# MCU.net
KiCad netlist of a schematic drawn in Altium Designer
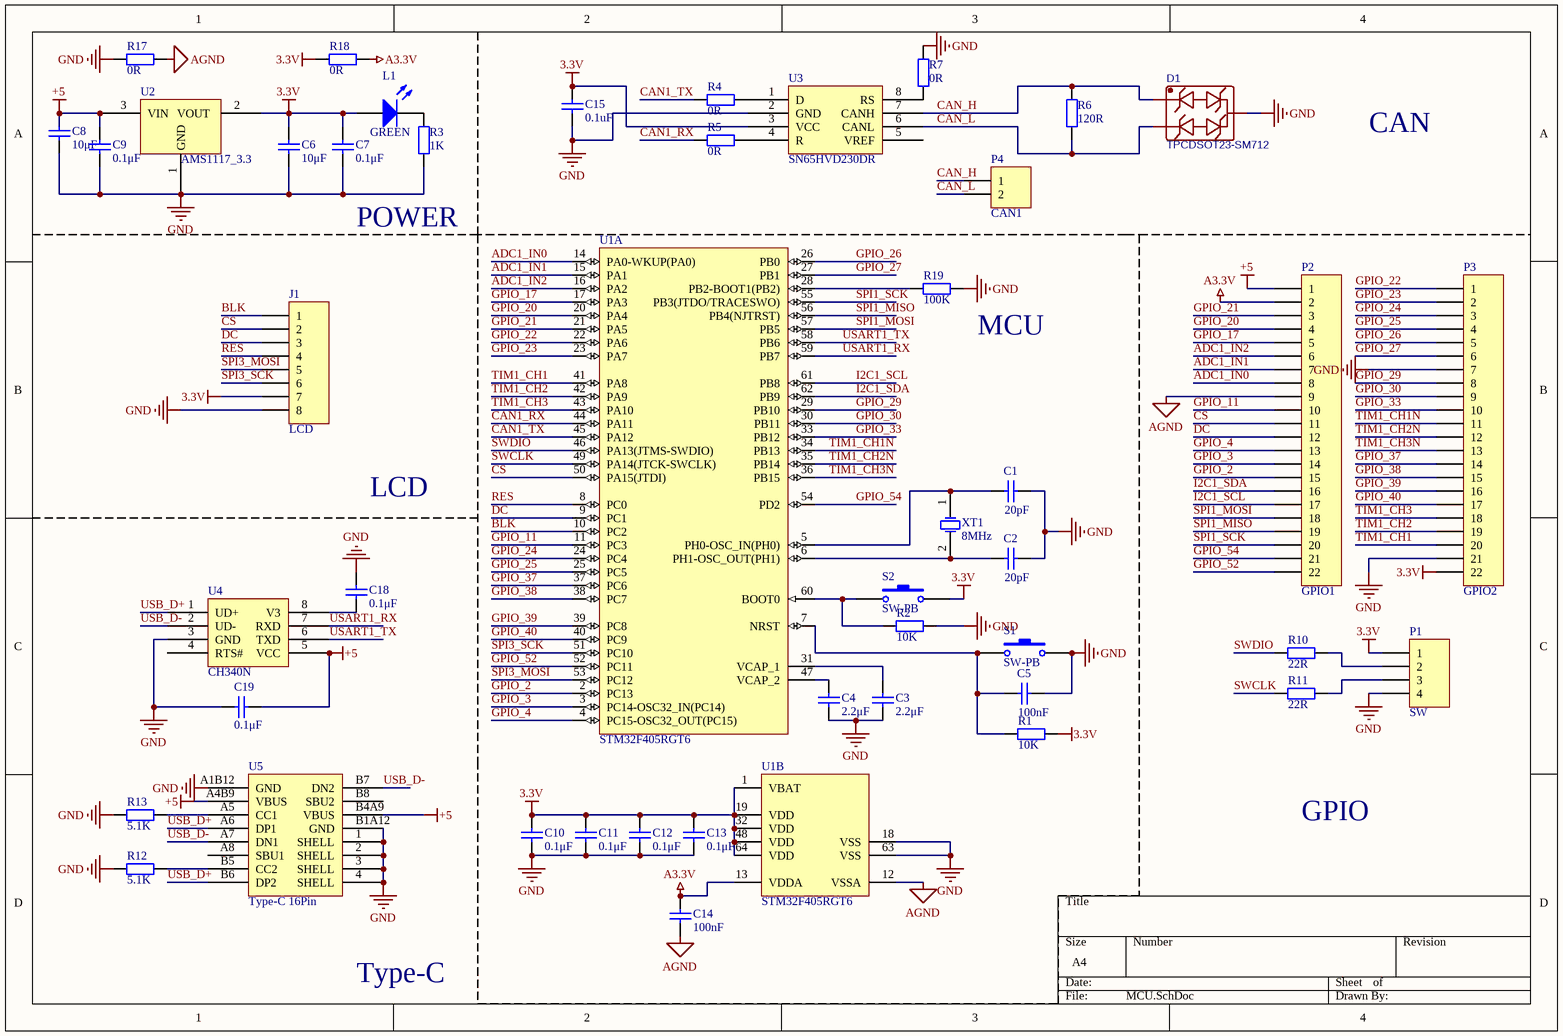
[diagram p0: MCU.SchDoc]

(export (version "E")
  (design (tool "Eeschema 10.0.6"))
  (components
    (comp (ref "C1")
      (value "20pF")
      (footprint "0402")
      (description "Capacitor (Semiconductor SIM Model)")
      (fields (field (name "PUBLISHER") "Altium Limited"))
      (libsource (lib "Miscellaneous Devices") (part "Cap Semi"))
    )
    (comp (ref "C2")
      (value "20pF")
      (footprint "0402")
      (description "Capacitor (Semiconductor SIM Model)")
      (fields (field (name "PUBLISHER") "Altium Limited"))
      (libsource (lib "Miscellaneous Devices") (part "Cap Semi"))
    )
    (comp (ref "C3")
      (value "2.2μF")
      (footprint "0402")
      (description "Capacitor (Semiconductor SIM Model)")
      (fields (field (name "PUBLISHER") "Altium Limited"))
      (libsource (lib "Miscellaneous Devices") (part "Cap Semi"))
    )
    (comp (ref "C4")
      (value "2.2μF")
      (footprint "0402")
      (description "Capacitor (Semiconductor SIM Model)")
      (fields (field (name "PUBLISHER") "Altium Limited"))
      (libsource (lib "Miscellaneous Devices") (part "Cap Semi"))
    )
    (comp (ref "C5")
      (value "100nF")
      (footprint "0402")
      (description "Capacitor (Semiconductor SIM Model)")
      (fields (field (name "PUBLISHER") "Altium Limited"))
      (libsource (lib "Miscellaneous Devices") (part "Cap Semi"))
    )
    (comp (ref "C6")
      (value "10μF")
      (footprint "0402")
      (description "Capacitor (Semiconductor SIM Model)")
      (fields (field (name "PUBLISHER") "Altium Limited"))
      (libsource (lib "Miscellaneous Devices") (part "Cap Semi"))
    )
    (comp (ref "C7")
      (value "0.1μF")
      (footprint "0402")
      (description "Capacitor (Semiconductor SIM Model)")
      (fields (field (name "PUBLISHER") "Altium Limited"))
      (libsource (lib "Miscellaneous Devices") (part "Cap Semi"))
    )
    (comp (ref "C8")
      (value "10μF")
      (footprint "0402")
      (description "Capacitor (Semiconductor SIM Model)")
      (fields (field (name "PUBLISHER") "Altium Limited"))
      (libsource (lib "Miscellaneous Devices") (part "Cap Semi"))
    )
    (comp (ref "C9")
      (value "0.1μF")
      (footprint "0402")
      (description "Capacitor (Semiconductor SIM Model)")
      (fields (field (name "PUBLISHER") "Altium Limited"))
      (libsource (lib "Miscellaneous Devices") (part "Cap Semi"))
    )
    (comp (ref "C10")
      (value "0.1μF")
      (footprint "0402")
      (description "Capacitor (Semiconductor SIM Model)")
      (fields (field (name "PUBLISHER") "Altium Limited"))
      (libsource (lib "Miscellaneous Devices") (part "Cap Semi"))
    )
    (comp (ref "C11")
      (value "0.1μF")
      (footprint "0402")
      (description "Capacitor (Semiconductor SIM Model)")
      (fields (field (name "PUBLISHER") "Altium Limited"))
      (libsource (lib "Miscellaneous Devices") (part "Cap Semi"))
    )
    (comp (ref "C12")
      (value "0.1μF")
      (footprint "0402")
      (description "Capacitor (Semiconductor SIM Model)")
      (fields (field (name "PUBLISHER") "Altium Limited"))
      (libsource (lib "Miscellaneous Devices") (part "Cap Semi"))
    )
    (comp (ref "C13")
      (value "0.1μF")
      (footprint "0402")
      (description "Capacitor (Semiconductor SIM Model)")
      (fields (field (name "PUBLISHER") "Altium Limited"))
      (libsource (lib "Miscellaneous Devices") (part "Cap Semi"))
    )
    (comp (ref "C14")
      (value "100nF")
      (footprint "0402")
      (description "Capacitor (Semiconductor SIM Model)")
      (fields (field (name "PUBLISHER") "Altium Limited"))
      (libsource (lib "Miscellaneous Devices") (part "Cap Semi"))
    )
    (comp (ref "C15")
      (value "0.1uF")
      (footprint "0402")
      (description "Capacitor (Semiconductor SIM Model)")
      (fields (field (name "PUBLISHER") "Altium Limited"))
      (libsource (lib "Miscellaneous Devices") (part "Cap Semi"))
    )
    (comp (ref "C18")
      (value "0.1μF")
      (footprint "0402")
      (description "Capacitor (Semiconductor SIM Model)")
      (fields (field (name "PUBLISHER") "Altium Limited"))
      (libsource (lib "Miscellaneous Devices") (part "Cap Semi"))
    )
    (comp (ref "C19")
      (value "0.1μF")
      (footprint "0402")
      (description "Capacitor (Semiconductor SIM Model)")
      (fields (field (name "PUBLISHER") "Altium Limited"))
      (libsource (lib "Miscellaneous Devices") (part "Cap Semi"))
    )
    (comp (ref "D1")
      (value "TPCDSOT23-SM712")
      (footprint "SOT23-3_L2.9-W1.6-P1.90-LS2.8-BR")
      (fields (field (name "BOM_SUPPLIER PART") "C558433") (field (name "CONTRIBUTOR") "LCSC"))
      (libsource (lib "Schlib1") (part "TPCDSOT23-SM712"))
    )
    (comp (ref "J1")
      (value "LCD")
      (footprint "HDR1X8")
      (description "Header, 8-Pin")
      (fields (field (name "PUBLISHER") "Altium Limited"))
      (libsource (lib "Miscellaneous Connectors") (part "Header 8"))
    )
    (comp (ref "L1")
      (value "GREEN")
      (footprint "0402-A")
      (description "Typical RED, GREEN, YELLOW, AMBER GaAs LED")
      (fields (field (name "PUBLISHER") "Altium Limited"))
      (libsource (lib "Miscellaneous Devices") (part "LED2"))
    )
    (comp (ref "P1")
      (value "SW")
      (footprint "HDR1X4")
      (description "Header, 4-Pin")
      (fields (field (name "PUBLISHER") "Altium Limited"))
      (libsource (lib "Miscellaneous Connectors") (part "Header 4"))
    )
    (comp (ref "P2")
      (value "GPIO1")
      (footprint "HDR1X22")
      (description "Header, 22-Pin")
      (fields (field (name "PUBLISHER") "Altium Limited"))
      (libsource (lib "Miscellaneous Connectors") (part "Header 22"))
    )
    (comp (ref "P3")
      (value "GPIO2")
      (footprint "HDR1X22")
      (description "Header, 22-Pin")
      (fields (field (name "PUBLISHER") "Altium Limited"))
      (libsource (lib "Miscellaneous Connectors") (part "Header 22"))
    )
    (comp (ref "P4")
      (value "CAN1")
      (footprint "FPC-SMD_2P-P2.00_DEALON_PH-2PWB")
      (description "Header, 2-Pin")
      (fields (field (name "PUBLISHER") "Altium Limited"))
      (libsource (lib "Miscellaneous Connectors") (part "Header 2"))
    )
    (comp (ref "R1")
      (value "10K")
      (footprint "0402")
      (description "Resistor")
      (fields (field (name "PUBLISHER") "Altium Limited"))
      (libsource (lib "") (part "Res2_1"))
    )
    (comp (ref "R2")
      (value "10K")
      (footprint "0402")
      (description "Resistor")
      (fields (field (name "PUBLISHER") "Altium Limited"))
      (libsource (lib "") (part "Res2_1"))
    )
    (comp (ref "R3")
      (value "1K")
      (footprint "0402")
      (description "Resistor")
      (fields (field (name "PUBLISHER") "Altium Limited"))
      (libsource (lib "Miscellaneous Devices") (part "Res2"))
    )
    (comp (ref "R4")
      (value "0R")
      (footprint "0402")
      (description "Resistor")
      (fields (field (name "PUBLISHER") "Altium Limited"))
      (libsource (lib "") (part "Res2_1"))
    )
    (comp (ref "R5")
      (value "0R")
      (footprint "0402")
      (description "Resistor")
      (fields (field (name "PUBLISHER") "Altium Limited"))
      (libsource (lib "") (part "Res2_1"))
    )
    (comp (ref "R6")
      (value "120R")
      (footprint "0402")
      (description "Resistor")
      (fields (field (name "PUBLISHER") "Altium Limited"))
      (libsource (lib "Miscellaneous Devices") (part "Res2"))
    )
    (comp (ref "R7")
      (value "0R")
      (footprint "0402")
      (description "Resistor")
      (fields (field (name "PUBLISHER") "Altium Limited"))
      (libsource (lib "Miscellaneous Devices") (part "Res2"))
    )
    (comp (ref "R10")
      (value "22R")
      (footprint "0402")
      (description "Resistor")
      (fields (field (name "PUBLISHER") "Altium Limited"))
      (libsource (lib "") (part "Res2_1"))
    )
    (comp (ref "R11")
      (value "22R")
      (footprint "0402")
      (description "Resistor")
      (fields (field (name "PUBLISHER") "Altium Limited"))
      (libsource (lib "") (part "Res2_1"))
    )
    (comp (ref "R12")
      (value "5.1K")
      (footprint "0402")
      (description "Resistor")
      (fields (field (name "PUBLISHER") "Altium Limited"))
      (libsource (lib "") (part "Res2_1"))
    )
    (comp (ref "R13")
      (value "5.1K")
      (footprint "0402")
      (description "Resistor")
      (fields (field (name "PUBLISHER") "Altium Limited"))
      (libsource (lib "") (part "Res2_1"))
    )
    (comp (ref "R17")
      (value "0R")
      (footprint "0402")
      (description "Resistor")
      (fields (field (name "PUBLISHER") "Altium Limited"))
      (libsource (lib "") (part "Res2_1"))
    )
    (comp (ref "R18")
      (value "0R")
      (footprint "0402")
      (description "Resistor")
      (fields (field (name "PUBLISHER") "Altium Limited"))
      (libsource (lib "") (part "Res2_1"))
    )
    (comp (ref "R19")
      (value "100K")
      (footprint "0402")
      (description "Resistor")
      (fields (field (name "PUBLISHER") "Altium Limited"))
      (libsource (lib "") (part "Res2_1"))
    )
    (comp (ref "S1")
      (value "SW-PB")
      (footprint "KEY-SMD_4P-L4.2-W3.2-P2.20-LS5.1-TL")
      (description "Switch")
      (fields (field (name "PUBLISHER") "Altium Limited"))
      (libsource (lib "Miscellaneous Devices") (part "SW-PB"))
    )
    (comp (ref "S2")
      (value "SW-PB")
      (footprint "KEY-SMD_4P-L4.2-W3.2-P2.20-LS5.1-TL")
      (description "Switch")
      (fields (field (name "PUBLISHER") "Altium Limited"))
      (libsource (lib "Miscellaneous Devices") (part "SW-PB"))
    )
    (comp (ref "U1")
      (value "STM32F405RGT6")
      (footprint "STM-LQFP64_N")
      (fields (field (name "MANUFACTURER") "STMicroelectronics"))
      (libsource (lib "STMicroelectronics STM32 F4") (part "STM32F405RGT6"))
    )
    (comp (ref "U2")
      (value "AMS1117_3.3")
      (footprint "SOT-89-3_L4.5-W2.5-P1.50-LS4.1-BL")
      (libsource (lib "Schlib1") (part "AMS1117_3.3 SOT-89"))
    )
    (comp (ref "U3")
      (value "SN65HVD230DR")
      (footprint "SN65HVD230DR-SOIC-8_L4.9-W3.9-P1.27-LS6.0-BL")
      (libsource (lib "Schlib1") (part "SN65HVD230DR"))
    )
    (comp (ref "U4")
      (value "CH340N")
      (footprint "CH340N-SOP-8_L4.9-W3.9-P1.27-LS6.0-BL")
      (libsource (lib "Schlib1") (part "CH340N"))
    )
    (comp (ref "U5")
      (value "Type-C 16Pin")
      (footprint "USB-C-SMD_TYPE-C16PIN")
      (libsource (lib "Schlib1") (part "Type-C 16Pin"))
    )
    (comp (ref "XT1")
      (value "8MHz")
      (footprint "OSC-SMD_L5.0-W3.2")
      (description "Crystal Oscillator")
      (fields (field (name "PUBLISHER") "Altium Limited"))
      (libsource (lib "Miscellaneous Devices") (part "XTAL"))
    )
  )
  (nets
    (net (code "1") (name "+5") (class "Default")
      (node (ref "C19") (pin "1") (pinfunction "1_1") (pintype "passive"))
      (node (ref "C8") (pin "2") (pinfunction "2_2") (pintype "passive"))
      (node (ref "C9") (pin "2") (pinfunction "2_2") (pintype "passive"))
      (node (ref "P2") (pin "1") (pinfunction "1_1") (pintype "passive"))
      (node (ref "U2") (pin "3") (pinfunction "VIN_3") (pintype "passive"))
      (node (ref "U4") (pin "5") (pinfunction "VCC_5") (pintype "passive"))
      (node (ref "U5") (pin "A4B9") (pinfunction "VBUS_A4B9") (pintype "passive"))
      (node (ref "U5") (pin "B4A9") (pinfunction "VBUS_B4A9") (pintype "passive"))
    )
    (net (code "2") (name "/ADC1_IN0") (class "Default")
      (node (ref "P2") (pin "8") (pinfunction "8_8") (pintype "passive"))
      (node (ref "U1") (pin "14") (pinfunction "PA0-WKUP(PA0)_14") (pintype "bidirectional"))
    )
    (net (code "3") (name "/ADC1_IN1") (class "Default")
      (node (ref "P2") (pin "7") (pinfunction "7_7") (pintype "passive"))
      (node (ref "U1") (pin "15") (pinfunction "PA1_15") (pintype "bidirectional"))
    )
    (net (code "4") (name "/ADC1_IN2") (class "Default")
      (node (ref "P2") (pin "6") (pinfunction "6_6") (pintype "passive"))
      (node (ref "U1") (pin "16") (pinfunction "PA2_16") (pintype "bidirectional"))
    )
    (net (code "5") (name "/BLK") (class "Default")
      (node (ref "J1") (pin "1") (pinfunction "1_1") (pintype "passive"))
      (node (ref "U1") (pin "10") (pinfunction "PC2_10") (pintype "bidirectional"))
    )
    (net (code "6") (name "/CAN1_RX") (class "Default")
      (node (ref "R5") (pin "1") (pinfunction "1_1") (pintype "passive"))
      (node (ref "U1") (pin "44") (pinfunction "PA11_44") (pintype "bidirectional"))
    )
    (net (code "7") (name "/CAN1_TX") (class "Default")
      (node (ref "R4") (pin "1") (pinfunction "1_1") (pintype "passive"))
      (node (ref "U1") (pin "45") (pinfunction "PA12_45") (pintype "bidirectional"))
    )
    (net (code "8") (name "/CAN_H") (class "Default")
      (node (ref "D1") (pin "1") (pinfunction "1_1") (pintype "passive"))
      (node (ref "P4") (pin "1") (pinfunction "1_1") (pintype "passive"))
      (node (ref "R6") (pin "2") (pinfunction "2_2") (pintype "passive"))
      (node (ref "U3") (pin "7") (pinfunction "CANH_7") (pintype "passive"))
    )
    (net (code "9") (name "/CAN_L") (class "Default")
      (node (ref "D1") (pin "2") (pinfunction "2_2") (pintype "passive"))
      (node (ref "P4") (pin "2") (pinfunction "2_2") (pintype "passive"))
      (node (ref "R6") (pin "1") (pinfunction "1_1") (pintype "passive"))
      (node (ref "U3") (pin "6") (pinfunction "CANL_6") (pintype "passive"))
    )
    (net (code "10") (name "/CS") (class "Default")
      (node (ref "J1") (pin "2") (pinfunction "2_2") (pintype "passive"))
      (node (ref "P2") (pin "11") (pinfunction "11_11") (pintype "passive"))
      (node (ref "U1") (pin "50") (pinfunction "PA15(JTDI)_50") (pintype "bidirectional"))
    )
    (net (code "11") (name "/DC") (class "Default")
      (node (ref "J1") (pin "3") (pinfunction "3_3") (pintype "passive"))
      (node (ref "P2") (pin "12") (pinfunction "12_12") (pintype "passive"))
      (node (ref "U1") (pin "9") (pinfunction "PC1_9") (pintype "bidirectional"))
    )
    (net (code "12") (name "/GPIO_2") (class "Default")
      (node (ref "P2") (pin "15") (pinfunction "15_15") (pintype "passive"))
      (node (ref "U1") (pin "2") (pinfunction "PC13_2") (pintype "bidirectional"))
    )
    (net (code "13") (name "/GPIO_3") (class "Default")
      (node (ref "P2") (pin "14") (pinfunction "14_14") (pintype "passive"))
      (node (ref "U1") (pin "3") (pinfunction "PC14-OSC32_IN(PC14)_3") (pintype "bidirectional"))
    )
    (net (code "14") (name "/GPIO_4") (class "Default")
      (node (ref "P2") (pin "13") (pinfunction "13_13") (pintype "passive"))
      (node (ref "U1") (pin "4") (pinfunction "PC15-OSC32_OUT(PC15)_4") (pintype "bidirectional"))
    )
    (net (code "15") (name "/GPIO_11") (class "Default")
      (node (ref "P2") (pin "10") (pinfunction "10_10") (pintype "passive"))
      (node (ref "U1") (pin "11") (pinfunction "PC3_11") (pintype "bidirectional"))
    )
    (net (code "16") (name "/GPIO_17") (class "Default")
      (node (ref "P2") (pin "5") (pinfunction "5_5") (pintype "passive"))
      (node (ref "U1") (pin "17") (pinfunction "PA3_17") (pintype "bidirectional"))
    )
    (net (code "17") (name "/GPIO_20") (class "Default")
      (node (ref "P2") (pin "4") (pinfunction "4_4") (pintype "passive"))
      (node (ref "U1") (pin "20") (pinfunction "PA4_20") (pintype "bidirectional"))
    )
    (net (code "18") (name "/GPIO_21") (class "Default")
      (node (ref "P2") (pin "3") (pinfunction "3_3") (pintype "passive"))
      (node (ref "U1") (pin "21") (pinfunction "PA5_21") (pintype "bidirectional"))
    )
    (net (code "19") (name "/GPIO_22") (class "Default")
      (node (ref "P3") (pin "1") (pinfunction "1_1") (pintype "passive"))
      (node (ref "U1") (pin "22") (pinfunction "PA6_22") (pintype "bidirectional"))
    )
    (net (code "20") (name "/GPIO_23") (class "Default")
      (node (ref "P3") (pin "2") (pinfunction "2_2") (pintype "passive"))
      (node (ref "U1") (pin "23") (pinfunction "PA7_23") (pintype "bidirectional"))
    )
    (net (code "21") (name "/GPIO_24") (class "Default")
      (node (ref "P3") (pin "3") (pinfunction "3_3") (pintype "passive"))
      (node (ref "U1") (pin "24") (pinfunction "PC4_24") (pintype "bidirectional"))
    )
    (net (code "22") (name "/GPIO_25") (class "Default")
      (node (ref "P3") (pin "4") (pinfunction "4_4") (pintype "passive"))
      (node (ref "U1") (pin "25") (pinfunction "PC5_25") (pintype "bidirectional"))
    )
    (net (code "23") (name "/GPIO_26") (class "Default")
      (node (ref "P3") (pin "5") (pinfunction "5_5") (pintype "passive"))
      (node (ref "U1") (pin "26") (pinfunction "PB0_26") (pintype "bidirectional"))
    )
    (net (code "24") (name "/GPIO_27") (class "Default")
      (node (ref "P3") (pin "6") (pinfunction "6_6") (pintype "passive"))
      (node (ref "U1") (pin "27") (pinfunction "PB1_27") (pintype "bidirectional"))
    )
    (net (code "25") (name "/GPIO_29") (class "Default")
      (node (ref "P3") (pin "8") (pinfunction "8_8") (pintype "passive"))
      (node (ref "U1") (pin "29") (pinfunction "PB10_29") (pintype "bidirectional"))
    )
    (net (code "26") (name "/GPIO_30") (class "Default")
      (node (ref "P3") (pin "9") (pinfunction "9_9") (pintype "passive"))
      (node (ref "U1") (pin "30") (pinfunction "PB11_30") (pintype "bidirectional"))
    )
    (net (code "27") (name "/GPIO_33") (class "Default")
      (node (ref "P3") (pin "10") (pinfunction "10_10") (pintype "passive"))
      (node (ref "U1") (pin "33") (pinfunction "PB12_33") (pintype "bidirectional"))
    )
    (net (code "28") (name "/GPIO_37") (class "Default")
      (node (ref "P3") (pin "14") (pinfunction "14_14") (pintype "passive"))
      (node (ref "U1") (pin "37") (pinfunction "PC6_37") (pintype "bidirectional"))
    )
    (net (code "29") (name "/GPIO_38") (class "Default")
      (node (ref "P3") (pin "15") (pinfunction "15_15") (pintype "passive"))
      (node (ref "U1") (pin "38") (pinfunction "PC7_38") (pintype "bidirectional"))
    )
    (net (code "30") (name "/GPIO_39") (class "Default")
      (node (ref "P3") (pin "16") (pinfunction "16_16") (pintype "passive"))
      (node (ref "U1") (pin "39") (pinfunction "PC8_39") (pintype "bidirectional"))
    )
    (net (code "31") (name "/GPIO_40") (class "Default")
      (node (ref "P3") (pin "17") (pinfunction "17_17") (pintype "passive"))
      (node (ref "U1") (pin "40") (pinfunction "PC9_40") (pintype "bidirectional"))
    )
    (net (code "32") (name "/GPIO_52") (class "Default")
      (node (ref "P2") (pin "22") (pinfunction "22_22") (pintype "passive"))
      (node (ref "U1") (pin "52") (pinfunction "PC11_52") (pintype "bidirectional"))
    )
    (net (code "33") (name "/GPIO_54") (class "Default")
      (node (ref "P2") (pin "21") (pinfunction "21_21") (pintype "passive"))
      (node (ref "U1") (pin "54") (pinfunction "PD2_54") (pintype "bidirectional"))
    )
    (net (code "34") (name "/I2C1_SCL") (class "Default")
      (node (ref "P2") (pin "17") (pinfunction "17_17") (pintype "passive"))
      (node (ref "U1") (pin "61") (pinfunction "PB8_61") (pintype "bidirectional"))
    )
    (net (code "35") (name "/I2C1_SDA") (class "Default")
      (node (ref "P2") (pin "16") (pinfunction "16_16") (pintype "passive"))
      (node (ref "U1") (pin "62") (pinfunction "PB9_62") (pintype "bidirectional"))
    )
    (net (code "36") (name "/RES") (class "Default")
      (node (ref "J1") (pin "4") (pinfunction "4_4") (pintype "passive"))
      (node (ref "U1") (pin "8") (pinfunction "PC0_8") (pintype "bidirectional"))
    )
    (net (code "37") (name "/SPI1_MISO") (class "Default")
      (node (ref "P2") (pin "19") (pinfunction "19_19") (pintype "passive"))
      (node (ref "U1") (pin "56") (pinfunction "PB4(NJTRST)_56") (pintype "bidirectional"))
    )
    (net (code "38") (name "/SPI1_MOSI") (class "Default")
      (node (ref "P2") (pin "18") (pinfunction "18_18") (pintype "passive"))
      (node (ref "U1") (pin "57") (pinfunction "PB5_57") (pintype "bidirectional"))
    )
    (net (code "39") (name "/SPI1_SCK") (class "Default")
      (node (ref "P2") (pin "20") (pinfunction "20_20") (pintype "passive"))
      (node (ref "U1") (pin "55") (pinfunction "PB3(JTDO/TRACESWO)_55") (pintype "bidirectional"))
    )
    (net (code "40") (name "/SPI3_MOSI") (class "Default")
      (node (ref "J1") (pin "5") (pinfunction "5_5") (pintype "passive"))
      (node (ref "U1") (pin "53") (pinfunction "PC12_53") (pintype "bidirectional"))
    )
    (net (code "41") (name "/SPI3_SCK") (class "Default")
      (node (ref "J1") (pin "6") (pinfunction "6_6") (pintype "passive"))
      (node (ref "U1") (pin "51") (pinfunction "PC10_51") (pintype "bidirectional"))
    )
    (net (code "42") (name "/SWCLK") (class "Default")
      (node (ref "R11") (pin "1") (pinfunction "1_1") (pintype "passive"))
      (node (ref "U1") (pin "49") (pinfunction "PA14(JTCK-SWCLK)_49") (pintype "bidirectional"))
    )
    (net (code "43") (name "/SWDIO") (class "Default")
      (node (ref "R10") (pin "1") (pinfunction "1_1") (pintype "passive"))
      (node (ref "U1") (pin "46") (pinfunction "PA13(JTMS-SWDIO)_46") (pintype "bidirectional"))
    )
    (net (code "44") (name "/TIM1_CH1") (class "Default")
      (node (ref "P3") (pin "20") (pinfunction "20_20") (pintype "passive"))
      (node (ref "U1") (pin "41") (pinfunction "PA8_41") (pintype "bidirectional"))
    )
    (net (code "45") (name "/TIM1_CH1N") (class "Default")
      (node (ref "P3") (pin "11") (pinfunction "11_11") (pintype "passive"))
      (node (ref "U1") (pin "34") (pinfunction "PB13_34") (pintype "bidirectional"))
    )
    (net (code "46") (name "/TIM1_CH2") (class "Default")
      (node (ref "P3") (pin "19") (pinfunction "19_19") (pintype "passive"))
      (node (ref "U1") (pin "42") (pinfunction "PA9_42") (pintype "bidirectional"))
    )
    (net (code "47") (name "/TIM1_CH2N") (class "Default")
      (node (ref "P3") (pin "12") (pinfunction "12_12") (pintype "passive"))
      (node (ref "U1") (pin "35") (pinfunction "PB14_35") (pintype "bidirectional"))
    )
    (net (code "48") (name "/TIM1_CH3") (class "Default")
      (node (ref "P3") (pin "18") (pinfunction "18_18") (pintype "passive"))
      (node (ref "U1") (pin "43") (pinfunction "PA10_43") (pintype "bidirectional"))
    )
    (net (code "49") (name "/TIM1_CH3N") (class "Default")
      (node (ref "P3") (pin "13") (pinfunction "13_13") (pintype "passive"))
      (node (ref "U1") (pin "36") (pinfunction "PB15_36") (pintype "bidirectional"))
    )
    (net (code "50") (name "/USART1_RX") (class "Default")
      (node (ref "U1") (pin "59") (pinfunction "PB7_59") (pintype "bidirectional"))
      (node (ref "U4") (pin "7") (pinfunction "RXD_7") (pintype "passive"))
    )
    (net (code "51") (name "/USART1_TX") (class "Default")
      (node (ref "U1") (pin "58") (pinfunction "PB6_58") (pintype "bidirectional"))
      (node (ref "U4") (pin "6") (pinfunction "TXD_6") (pintype "passive"))
    )
    (net (code "52") (name "/USB_D+") (class "Default")
      (node (ref "U4") (pin "1") (pinfunction "UD+_1") (pintype "passive"))
      (node (ref "U5") (pin "A6") (pinfunction "DP1_A6") (pintype "passive"))
      (node (ref "U5") (pin "B6") (pinfunction "DP2_B6") (pintype "passive"))
    )
    (net (code "53") (name "/USB_D-") (class "Default")
      (node (ref "U4") (pin "2") (pinfunction "UD-_2") (pintype "passive"))
      (node (ref "U5") (pin "A7") (pinfunction "DN1_A7") (pintype "passive"))
      (node (ref "U5") (pin "B7") (pinfunction "DN2_B7") (pintype "passive"))
    )
    (net (code "54") (name "3.3V") (class "Default")
      (node (ref "C10") (pin "2") (pinfunction "2_2") (pintype "passive"))
      (node (ref "C11") (pin "2") (pinfunction "2_2") (pintype "passive"))
      (node (ref "C12") (pin "2") (pinfunction "2_2") (pintype "passive"))
      (node (ref "C13") (pin "2") (pinfunction "2_2") (pintype "passive"))
      (node (ref "C15") (pin "2") (pinfunction "2_2") (pintype "passive"))
      (node (ref "C6") (pin "2") (pinfunction "2_2") (pintype "passive"))
      (node (ref "C7") (pin "2") (pinfunction "2_2") (pintype "passive"))
      (node (ref "J1") (pin "7") (pinfunction "7_7") (pintype "passive"))
      (node (ref "L1") (pin "1") (pinfunction "A_1") (pintype "passive"))
      (node (ref "P1") (pin "1") (pinfunction "1_1") (pintype "passive"))
      (node (ref "P3") (pin "22") (pinfunction "22_22") (pintype "passive"))
      (node (ref "R1") (pin "2") (pinfunction "2_2") (pintype "passive"))
      (node (ref "R18") (pin "1") (pinfunction "1_1") (pintype "passive"))
      (node (ref "S2") (pin "2") (pinfunction "2_2") (pintype "passive"))
      (node (ref "U1") (pin "1") (pinfunction "VBAT_1") (pintype "power_in"))
      (node (ref "U1") (pin "19") (pinfunction "VDD_19") (pintype "power_in"))
      (node (ref "U1") (pin "32") (pinfunction "VDD_32") (pintype "power_in"))
      (node (ref "U1") (pin "48") (pinfunction "VDD_48") (pintype "power_in"))
      (node (ref "U1") (pin "64") (pinfunction "VDD_64") (pintype "power_in"))
      (node (ref "U2") (pin "2") (pinfunction "VOUT_2") (pintype "passive"))
      (node (ref "U3") (pin "3") (pinfunction "VCC_3") (pintype "passive"))
    )
    (net (code "55") (name "A3.3V") (class "Default")
      (node (ref "C14") (pin "2") (pinfunction "2_2") (pintype "passive"))
      (node (ref "P2") (pin "2") (pinfunction "2_2") (pintype "passive"))
      (node (ref "R18") (pin "2") (pinfunction "2_2") (pintype "passive"))
      (node (ref "U1") (pin "13") (pinfunction "VDDA_13") (pintype "power_in"))
    )
    (net (code "56") (name "AGND") (class "Default")
      (node (ref "C14") (pin "1") (pinfunction "1_1") (pintype "passive"))
      (node (ref "P2") (pin "9") (pinfunction "9_9") (pintype "passive"))
      (node (ref "R17") (pin "2") (pinfunction "2_2") (pintype "passive"))
      (node (ref "U1") (pin "12") (pinfunction "VSSA_12") (pintype "power_in"))
    )
    (net (code "57") (name "GND") (class "Default")
      (node (ref "C1") (pin "2") (pinfunction "2_2") (pintype "passive"))
      (node (ref "C10") (pin "1") (pinfunction "1_1") (pintype "passive"))
      (node (ref "C11") (pin "1") (pinfunction "1_1") (pintype "passive"))
      (node (ref "C12") (pin "1") (pinfunction "1_1") (pintype "passive"))
      (node (ref "C13") (pin "1") (pinfunction "1_1") (pintype "passive"))
      (node (ref "C15") (pin "1") (pinfunction "1_1") (pintype "passive"))
      (node (ref "C18") (pin "2") (pinfunction "2_2") (pintype "passive"))
      (node (ref "C19") (pin "2") (pinfunction "2_2") (pintype "passive"))
      (node (ref "C2") (pin "2") (pinfunction "2_2") (pintype "passive"))
      (node (ref "C3") (pin "1") (pinfunction "1_1") (pintype "passive"))
      (node (ref "C4") (pin "1") (pinfunction "1_1") (pintype "passive"))
      (node (ref "C5") (pin "2") (pinfunction "2_2") (pintype "passive"))
      (node (ref "C6") (pin "1") (pinfunction "1_1") (pintype "passive"))
      (node (ref "C7") (pin "1") (pinfunction "1_1") (pintype "passive"))
      (node (ref "C8") (pin "1") (pinfunction "1_1") (pintype "passive"))
      (node (ref "C9") (pin "1") (pinfunction "1_1") (pintype "passive"))
      (node (ref "D1") (pin "3") (pinfunction "3_3") (pintype "passive"))
      (node (ref "J1") (pin "8") (pinfunction "8_8") (pintype "passive"))
      (node (ref "P1") (pin "4") (pinfunction "4_4") (pintype "passive"))
      (node (ref "P3") (pin "21") (pinfunction "21_21") (pintype "passive"))
      (node (ref "P3") (pin "7") (pinfunction "7_7") (pintype "passive"))
      (node (ref "R12") (pin "1") (pinfunction "1_1") (pintype "passive"))
      (node (ref "R13") (pin "1") (pinfunction "1_1") (pintype "passive"))
      (node (ref "R17") (pin "1") (pinfunction "1_1") (pintype "passive"))
      (node (ref "R19") (pin "2") (pinfunction "2_2") (pintype "passive"))
      (node (ref "R2") (pin "2") (pinfunction "2_2") (pintype "passive"))
      (node (ref "R3") (pin "1") (pinfunction "1_1") (pintype "passive"))
      (node (ref "R7") (pin "2") (pinfunction "2_2") (pintype "passive"))
      (node (ref "S1") (pin "2") (pinfunction "2_2") (pintype "passive"))
      (node (ref "U1") (pin "18") (pinfunction "VSS_18") (pintype "power_in"))
      (node (ref "U1") (pin "63") (pinfunction "VSS_63") (pintype "power_in"))
      (node (ref "U2") (pin "1") (pinfunction "GND_1") (pintype "passive"))
      (node (ref "U3") (pin "2") (pinfunction "GND_2") (pintype "passive"))
      (node (ref "U4") (pin "3") (pinfunction "GND_3") (pintype "passive"))
      (node (ref "U5") (pin "1") (pinfunction "SHELL_1") (pintype "passive"))
      (node (ref "U5") (pin "2") (pinfunction "SHELL_2") (pintype "passive"))
      (node (ref "U5") (pin "3") (pinfunction "SHELL_3") (pintype "passive"))
      (node (ref "U5") (pin "4") (pinfunction "SHELL_4") (pintype "passive"))
      (node (ref "U5") (pin "A1B12") (pinfunction "GND_A1B12") (pintype "passive"))
      (node (ref "U5") (pin "B1A12") (pinfunction "GND_B1A12") (pintype "passive"))
    )
    (net (code "58") (name "Net-(L1-K)") (class "Default")
      (node (ref "L1") (pin "2") (pinfunction "K_2") (pintype "passive"))
      (node (ref "R3") (pin "2") (pinfunction "2_2") (pintype "passive"))
    )
    (net (code "59") (name "Net-(P1-Pad2)") (class "Default")
      (node (ref "P1") (pin "2") (pinfunction "2_2") (pintype "passive"))
      (node (ref "R10") (pin "2") (pinfunction "2_2") (pintype "passive"))
    )
    (net (code "60") (name "Net-(P1-Pad3)") (class "Default")
      (node (ref "P1") (pin "3") (pinfunction "3_3") (pintype "passive"))
      (node (ref "R11") (pin "2") (pinfunction "2_2") (pintype "passive"))
    )
    (net (code "61") (name "Net-(U1A-BOOT0)") (class "Default")
      (node (ref "R2") (pin "1") (pinfunction "1_1") (pintype "passive"))
      (node (ref "S2") (pin "1") (pinfunction "1_1") (pintype "passive"))
      (node (ref "U1") (pin "60") (pinfunction "BOOT0_60") (pintype "input"))
    )
    (net (code "62") (name "Net-(U1A-NRST)") (class "Default")
      (node (ref "C5") (pin "1") (pinfunction "1_1") (pintype "passive"))
      (node (ref "R1") (pin "1") (pinfunction "1_1") (pintype "passive"))
      (node (ref "S1") (pin "1") (pinfunction "1_1") (pintype "passive"))
      (node (ref "U1") (pin "7") (pinfunction "NRST_7") (pintype "bidirectional"))
    )
    (net (code "63") (name "Net-(U1A-PB2-BOOT1(PB2))") (class "Default")
      (node (ref "R19") (pin "1") (pinfunction "1_1") (pintype "passive"))
      (node (ref "U1") (pin "28") (pinfunction "PB2-BOOT1(PB2)_28") (pintype "bidirectional"))
    )
    (net (code "64") (name "Net-(U1A-PH0-OSC_IN(PH0))") (class "Default")
      (node (ref "C1") (pin "1") (pinfunction "1_1") (pintype "passive"))
      (node (ref "U1") (pin "5") (pinfunction "PH0-OSC_IN(PH0)_5") (pintype "bidirectional"))
      (node (ref "XT1") (pin "1") (pinfunction "OSC1_1") (pintype "passive"))
    )
    (net (code "65") (name "Net-(U1A-PH1-OSC_OUT(PH1))") (class "Default")
      (node (ref "C2") (pin "1") (pinfunction "1_1") (pintype "passive"))
      (node (ref "U1") (pin "6") (pinfunction "PH1-OSC_OUT(PH1)_6") (pintype "bidirectional"))
      (node (ref "XT1") (pin "2") (pinfunction "OSC2_2") (pintype "passive"))
    )
    (net (code "66") (name "Net-(U1A-VCAP_1)") (class "Default")
      (node (ref "C3") (pin "2") (pinfunction "2_2") (pintype "passive"))
      (node (ref "U1") (pin "31") (pinfunction "VCAP_1_31") (pintype "power_in"))
    )
    (net (code "67") (name "Net-(U1A-VCAP_2)") (class "Default")
      (node (ref "C4") (pin "2") (pinfunction "2_2") (pintype "passive"))
      (node (ref "U1") (pin "47") (pinfunction "VCAP_2_47") (pintype "power_in"))
    )
    (net (code "68") (name "Net-(U3-D)") (class "Default")
      (node (ref "R4") (pin "2") (pinfunction "2_2") (pintype "passive"))
      (node (ref "U3") (pin "1") (pinfunction "D_1") (pintype "passive"))
    )
    (net (code "69") (name "Net-(U3-R)") (class "Default")
      (node (ref "R5") (pin "2") (pinfunction "2_2") (pintype "passive"))
      (node (ref "U3") (pin "4") (pinfunction "R_4") (pintype "passive"))
    )
    (net (code "70") (name "Net-(U3-RS)") (class "Default")
      (node (ref "R7") (pin "1") (pinfunction "1_1") (pintype "passive"))
      (node (ref "U3") (pin "8") (pinfunction "RS_8") (pintype "passive"))
    )
    (net (code "71") (name "Net-(U4-V3)") (class "Default")
      (node (ref "C18") (pin "1") (pinfunction "1_1") (pintype "passive"))
      (node (ref "U4") (pin "8") (pinfunction "V3_8") (pintype "passive"))
    )
    (net (code "72") (name "Net-(U5-CC1)") (class "Default")
      (node (ref "R13") (pin "2") (pinfunction "2_2") (pintype "passive"))
      (node (ref "U5") (pin "A5") (pinfunction "CC1_A5") (pintype "passive"))
    )
    (net (code "73") (name "Net-(U5-CC2)") (class "Default")
      (node (ref "R12") (pin "2") (pinfunction "2_2") (pintype "passive"))
      (node (ref "U5") (pin "B5") (pinfunction "CC2_B5") (pintype "passive"))
    )
    (net (code "74") (name "unconnected-(U3-VREF-Pad5)") (class "Default")
      (node (ref "U3") (pin "5") (pinfunction "VREF_5") (pintype "passive"))
    )
    (net (code "75") (name "unconnected-(U4-RTS#-Pad4)") (class "Default")
      (node (ref "U4") (pin "4") (pinfunction "RTS#_4") (pintype "passive"))
    )
    (net (code "76") (name "unconnected-(U5-SBU1-PadA8)") (class "Default")
      (node (ref "U5") (pin "A8") (pinfunction "SBU1_A8") (pintype "passive"))
    )
    (net (code "77") (name "unconnected-(U5-SBU2-PadB8)") (class "Default")
      (node (ref "U5") (pin "B8") (pinfunction "SBU2_B8") (pintype "passive"))
    )
  )
)
